# MAKO_pH_sensor_schematic.net
KiCad netlist of a schematic drawn in Altium Designer
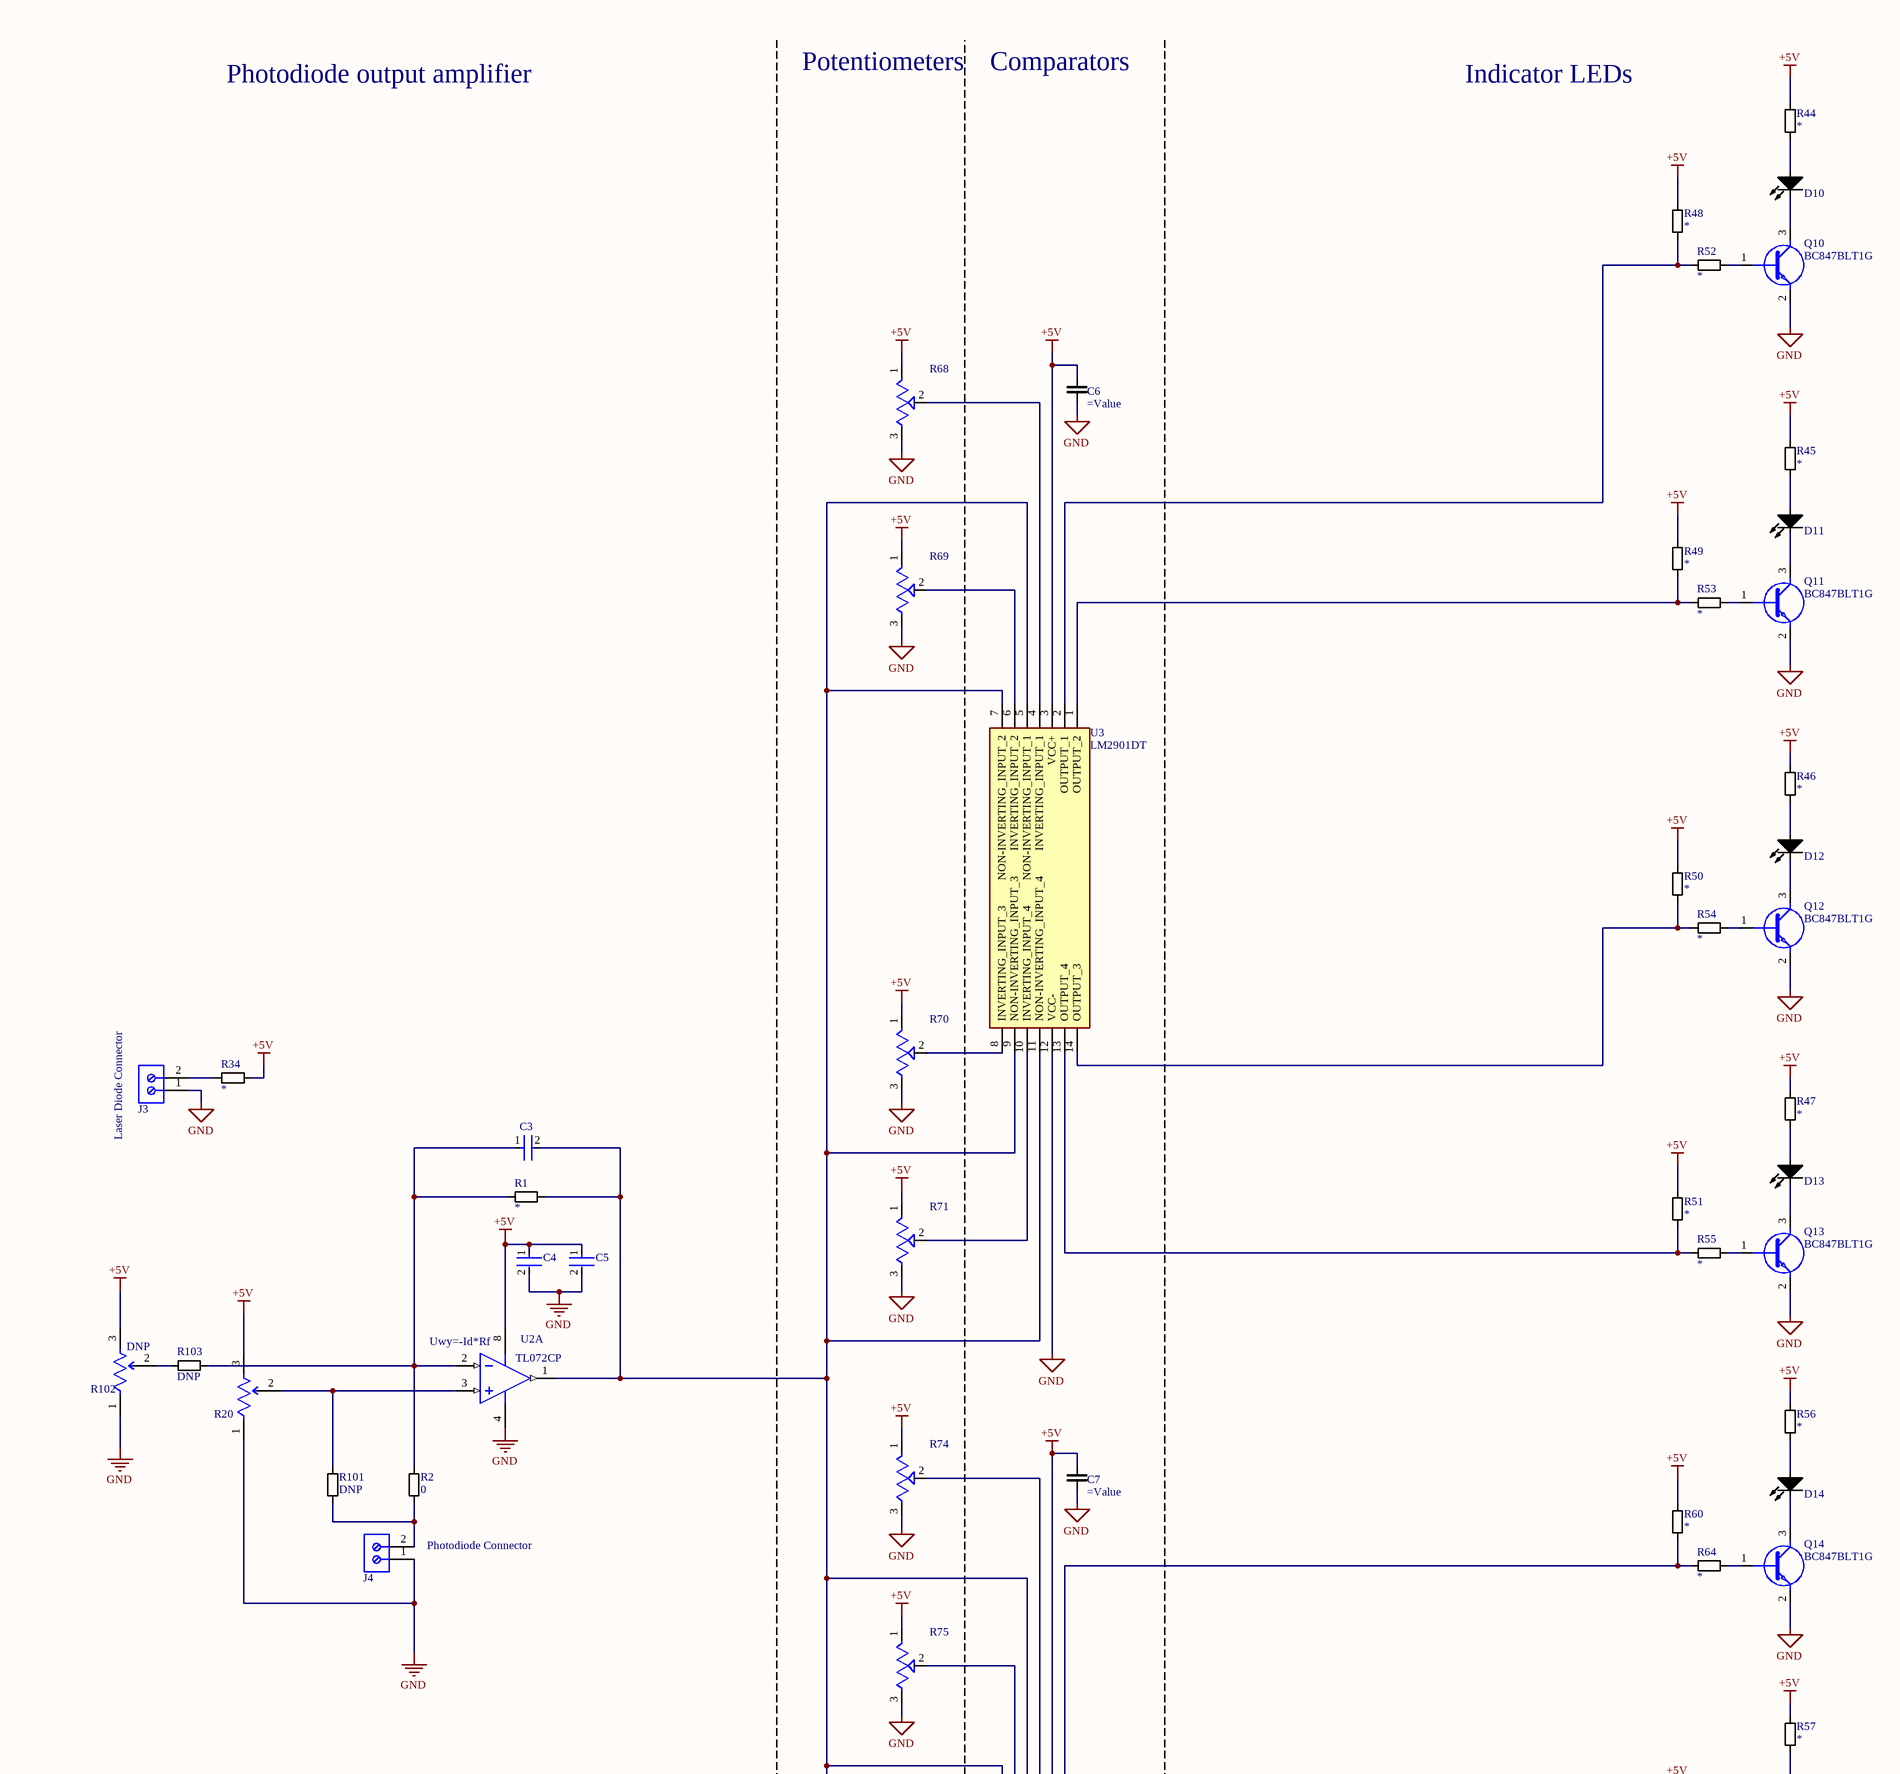
[diagram p0: MAKO_pH_sensor_schematic.SchDoc, top]
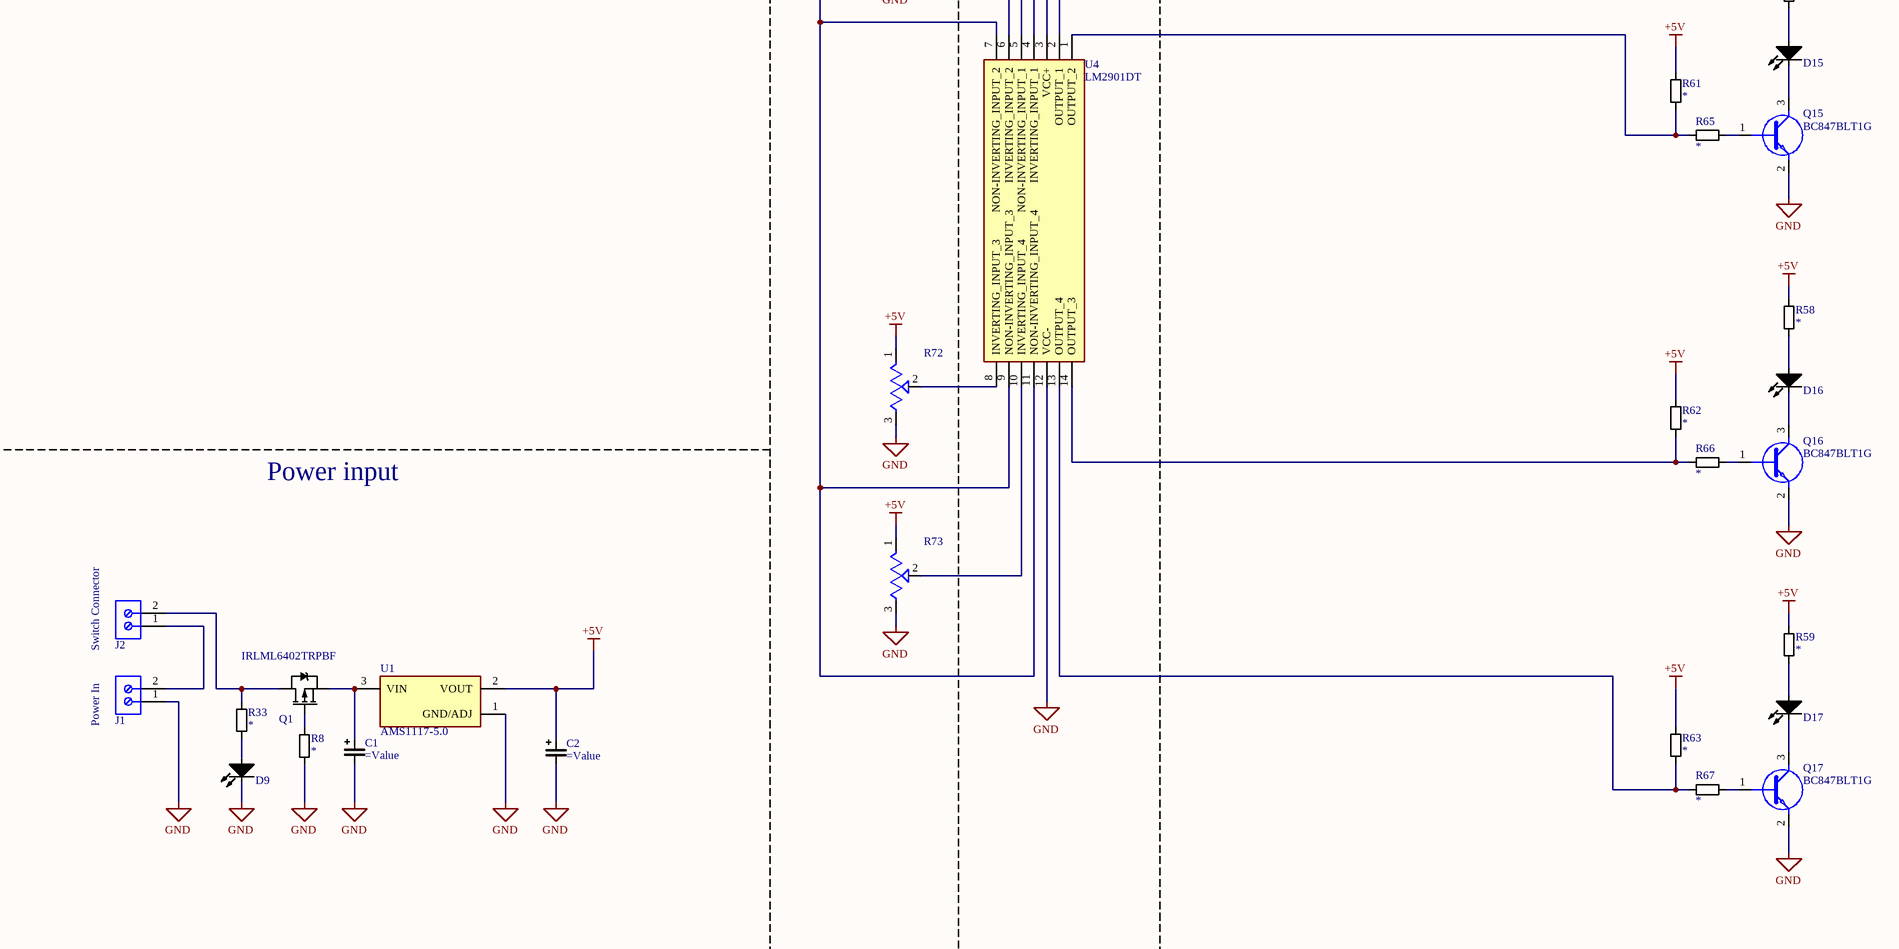
[diagram p1: MAKO_pH_sensor_schematic.SchDoc, bottom]

(export (version "E")
  (design (tool "Eeschema 10.0.6"))
  (components
    (comp (ref "C1")
      (value "~")
      (footprint "CAPAE530X610N:CAPAE530X610N")
      (description "Ceramic capacitor")
      (libsource (lib "Cap") (part "CapPol"))
    )
    (comp (ref "C2")
      (value "~")
      (footprint "CAPAE530X610N:CAPAE530X610N")
      (description "Ceramic capacitor")
      (libsource (lib "Cap") (part "CapPol"))
    )
    (comp (ref "C3")
      (value "C1206C102KGRACTU")
      (footprint "FP-C1206C-EF-MFG")
      (description "CAP CER 1000PF 2KV X7R 1206")
      (fields (field (name "VOLTAGE") "2kV") (field (name "TOLERANCE") "10%"))
      (libsource (lib "Altium Content Vault") (part "b4654b650e69147ec39a6b967a45e02"))
    )
    (comp (ref "C4")
      (value "C1206C104M5RACTU")
      (footprint "FP-C1206C-EB-MFG")
      (description "CAP CER 0.1UF 50V X7R 1206")
      (fields
        (field (name "OCTOPART") "https://octopart.com/c1206c104m5ractu-kemet-129344")
        (field (name "TOLERANCE") "0.2")
      )
      (libsource (lib "Altium Content Vault") (part "b4654b650e69147ec39a6b967a45e02"))
    )
    (comp (ref "C5")
      (value "C1206C104M5RACTU")
      (footprint "FP-C1206C-EB-MFG")
      (description "CAP CER 0.1UF 50V X7R 1206")
      (fields
        (field (name "OCTOPART") "https://octopart.com/c1206c104m5ractu-kemet-129344")
        (field (name "TOLERANCE") "0.2")
      )
      (libsource (lib "Altium Content Vault") (part "b4654b650e69147ec39a6b967a45e02"))
    )
    (comp (ref "C6")
      (value "~")
      (footprint "CAPC1608X90N")
      (description "Ceramic capacitor")
      (libsource (lib "Cap") (part "Cap"))
    )
    (comp (ref "C7")
      (value "~")
      (footprint "CAPC1608X90N")
      (description "Ceramic capacitor")
      (libsource (lib "Cap") (part "Cap"))
    )
    (comp (ref "D9")
      (value "~")
      (footprint "151033RS03000:151033RS03000")
      (libsource (lib "LED") (part "LED"))
    )
    (comp (ref "D10") (value "~") (footprint "151033RS03000") (libsource (lib "LED") (part "LED")))
    (comp (ref "D11") (value "~") (footprint "151033RS03000") (libsource (lib "LED") (part "LED")))
    (comp (ref "D12") (value "~") (footprint "151033RS03000") (libsource (lib "LED") (part "LED")))
    (comp (ref "D13") (value "~") (footprint "151033RS03000") (libsource (lib "LED") (part "LED")))
    (comp (ref "D14") (value "~") (footprint "151033RS03000") (libsource (lib "LED") (part "LED")))
    (comp (ref "D15")
      (value "~")
      (footprint "151033RS03000:151033RS03000")
      (libsource (lib "LED") (part "LED"))
    )
    (comp (ref "D16")
      (value "~")
      (footprint "151033RS03000:151033RS03000")
      (libsource (lib "LED") (part "LED"))
    )
    (comp (ref "D17")
      (value "~")
      (footprint "151033RS03000:151033RS03000")
      (libsource (lib "LED") (part "LED"))
    )
    (comp (ref "J1")
      (value "691101710002")
      (footprint "RHDRRA2W95P0X500_1X2_1120X900X1280P:RHDRRA2W95P0X500_1X2_1120X900X1280P")
      (description "WR-TBL Series 101 Horizontal Entry Modular, THT, pitch 5mm, 2p")
      (fields (field (name "MANUFACTURER") "Wurth Elektronik"))
      (libsource (lib "Altium_WR-TBL (rev23e)") (part "691101710002"))
    )
    (comp (ref "J2")
      (value "691101710002")
      (footprint "RHDRRA2W95P0X500_1X2_1120X900X1280P:RHDRRA2W95P0X500_1X2_1120X900X1280P")
      (description "WR-TBL Series 101 Horizontal Entry Modular, THT, pitch 5mm, 2p")
      (fields (field (name "MANUFACTURER") "Wurth Elektronik"))
      (libsource (lib "Altium_WR-TBL (rev23e)") (part "691101710002"))
    )
    (comp (ref "J3")
      (value "691101710002")
      (footprint "RHDRRA2W95P0X500_1X2_1120X900X1280P:RHDRRA2W95P0X500_1X2_1120X900X1280P")
      (description "WR-TBL Series 101 Horizontal Entry Modular, THT, pitch 5mm, 2p")
      (fields (field (name "MANUFACTURER") "Wurth Elektronik"))
      (libsource (lib "Altium_WR-TBL (rev23e)") (part "691101710002"))
    )
    (comp (ref "J4")
      (value "691101710002")
      (footprint "RHDRRA2W95P0X500_1X2_1120X900X1280P:RHDRRA2W95P0X500_1X2_1120X900X1280P")
      (description "WR-TBL Series 101 Horizontal Entry Modular, THT, pitch 5mm, 2p")
      (fields (field (name "MANUFACTURER") "Wurth Elektronik"))
      (libsource (lib "Altium_WR-TBL (rev23e)") (part "691101710002"))
    )
    (comp (ref "Q1")
      (value "IRLML6402TRPBF")
      (footprint "SOT95P237X112-3N:SOT95P237X112-3N")
      (libsource (lib "PMOSFET") (part "PMOSFET"))
    )
    (comp (ref "Q10")
      (value "BC847BLT1G")
      (footprint "SOT96P237X111-3N")
      (fields (field (name "MOUSER PART NUMBER") "863-BC847BLT1G"))
      (libsource (lib "BC847BLT1G") (part "BC847BLT1G"))
    )
    (comp (ref "Q11")
      (value "BC847BLT1G")
      (footprint "SOT96P237X111-3N")
      (fields (field (name "MOUSER PART NUMBER") "863-BC847BLT1G"))
      (libsource (lib "BC847BLT1G") (part "BC847BLT1G"))
    )
    (comp (ref "Q12")
      (value "BC847BLT1G")
      (footprint "SOT96P237X111-3N")
      (fields (field (name "MOUSER PART NUMBER") "863-BC847BLT1G"))
      (libsource (lib "BC847BLT1G") (part "BC847BLT1G"))
    )
    (comp (ref "Q13")
      (value "BC847BLT1G")
      (footprint "SOT96P237X111-3N")
      (fields (field (name "MOUSER PART NUMBER") "863-BC847BLT1G"))
      (libsource (lib "BC847BLT1G") (part "BC847BLT1G"))
    )
    (comp (ref "Q14")
      (value "BC847BLT1G")
      (footprint "SOT96P237X111-3N")
      (fields (field (name "MOUSER PART NUMBER") "863-BC847BLT1G"))
      (libsource (lib "BC847BLT1G") (part "BC847BLT1G"))
    )
    (comp (ref "Q15")
      (value "BC847BLT1G")
      (footprint "SOT96P237X111-3N")
      (fields (field (name "MOUSER PART NUMBER") "863-BC847BLT1G"))
      (libsource (lib "BC847BLT1G") (part "BC847BLT1G"))
    )
    (comp (ref "Q16")
      (value "BC847BLT1G")
      (footprint "SOT96P237X111-3N")
      (fields (field (name "MOUSER PART NUMBER") "863-BC847BLT1G"))
      (libsource (lib "BC847BLT1G") (part "BC847BLT1G"))
    )
    (comp (ref "Q17")
      (value "BC847BLT1G")
      (footprint "SOT96P237X111-3N")
      (fields (field (name "MOUSER PART NUMBER") "863-BC847BLT1G"))
      (libsource (lib "BC847BLT1G") (part "BC847BLT1G"))
    )
    (comp (ref "R1")
      (value "*")
      (footprint "CAPC1608X90N")
      (description "Resistor")
      (libsource (lib "RES") (part "RES"))
    )
    (comp (ref "R2")
      (value "0")
      (footprint "CAPC1608X90N")
      (description "Resistor")
      (libsource (lib "RES") (part "RES"))
    )
    (comp (ref "R8")
      (value "*")
      (footprint "CAPC1608X90N")
      (description "Resistor")
      (libsource (lib "RES") (part "RES"))
    )
    (comp (ref "R20")
      (value "3296W-1-103LF")
      (footprint "FP-3296W-MFG")
      (description "TRIMMER 10K OHM 0.5W PC PIN TOP\r\n3296W-1-103LF")
      (fields (field (name "TOLERANCE") "10%"))
      (libsource (lib "Altium Content Vault") (part "2dcfd2547301a7d3209a5e99acfd772"))
    )
    (comp (ref "R33")
      (value "*")
      (footprint "CAPC1608X90N")
      (description "Resistor")
      (libsource (lib "RES") (part "RES"))
    )
    (comp (ref "R34")
      (value "*")
      (footprint "CAPC1608X90N")
      (description "Resistor")
      (libsource (lib "RES") (part "RES"))
    )
    (comp (ref "R44")
      (value "*")
      (footprint "CAPC1608X90N")
      (description "Resistor")
      (libsource (lib "RES") (part "RES"))
    )
    (comp (ref "R45")
      (value "*")
      (footprint "CAPC1608X90N")
      (description "Resistor")
      (libsource (lib "RES") (part "RES"))
    )
    (comp (ref "R46")
      (value "*")
      (footprint "CAPC1608X90N")
      (description "Resistor")
      (libsource (lib "RES") (part "RES"))
    )
    (comp (ref "R47")
      (value "*")
      (footprint "CAPC1608X90N")
      (description "Resistor")
      (libsource (lib "RES") (part "RES"))
    )
    (comp (ref "R48")
      (value "*")
      (footprint "CAPC1608X90N")
      (description "Resistor")
      (libsource (lib "RES") (part "RES"))
    )
    (comp (ref "R49")
      (value "*")
      (footprint "CAPC1608X90N")
      (description "Resistor")
      (libsource (lib "RES") (part "RES"))
    )
    (comp (ref "R50")
      (value "*")
      (footprint "CAPC1608X90N")
      (description "Resistor")
      (libsource (lib "RES") (part "RES"))
    )
    (comp (ref "R51")
      (value "*")
      (footprint "CAPC1608X90N")
      (description "Resistor")
      (libsource (lib "RES") (part "RES"))
    )
    (comp (ref "R52")
      (value "*")
      (footprint "CAPC1608X90N")
      (description "Resistor")
      (libsource (lib "RES") (part "RES"))
    )
    (comp (ref "R53")
      (value "*")
      (footprint "CAPC1608X90N")
      (description "Resistor")
      (libsource (lib "RES") (part "RES"))
    )
    (comp (ref "R54")
      (value "*")
      (footprint "CAPC1608X90N")
      (description "Resistor")
      (libsource (lib "RES") (part "RES"))
    )
    (comp (ref "R55")
      (value "*")
      (footprint "CAPC1608X90N")
      (description "Resistor")
      (libsource (lib "RES") (part "RES"))
    )
    (comp (ref "R56")
      (value "*")
      (footprint "CAPC1608X90N")
      (description "Resistor")
      (libsource (lib "RES") (part "RES"))
    )
    (comp (ref "R57")
      (value "*")
      (footprint "CAPC1608X90N")
      (description "Resistor")
      (libsource (lib "RES") (part "RES"))
    )
    (comp (ref "R58")
      (value "*")
      (footprint "CAPC1608X90N")
      (description "Resistor")
      (libsource (lib "RES") (part "RES"))
    )
    (comp (ref "R59")
      (value "*")
      (footprint "CAPC1608X90N")
      (description "Resistor")
      (libsource (lib "RES") (part "RES"))
    )
    (comp (ref "R60")
      (value "*")
      (footprint "CAPC1608X90N")
      (description "Resistor")
      (libsource (lib "RES") (part "RES"))
    )
    (comp (ref "R61")
      (value "*")
      (footprint "CAPC1608X90N")
      (description "Resistor")
      (libsource (lib "RES") (part "RES"))
    )
    (comp (ref "R62")
      (value "*")
      (footprint "CAPC1608X90N")
      (description "Resistor")
      (libsource (lib "RES") (part "RES"))
    )
    (comp (ref "R63")
      (value "*")
      (footprint "CAPC1608X90N")
      (description "Resistor")
      (libsource (lib "RES") (part "RES"))
    )
    (comp (ref "R64")
      (value "*")
      (footprint "CAPC1608X90N")
      (description "Resistor")
      (libsource (lib "RES") (part "RES"))
    )
    (comp (ref "R65")
      (value "*")
      (footprint "CAPC1608X90N")
      (description "Resistor")
      (libsource (lib "RES") (part "RES"))
    )
    (comp (ref "R66")
      (value "*")
      (footprint "CAPC1608X90N")
      (description "Resistor")
      (libsource (lib "RES") (part "RES"))
    )
    (comp (ref "R67")
      (value "*")
      (footprint "CAPC1608X90N")
      (description "Resistor")
      (libsource (lib "RES") (part "RES"))
    )
    (comp (ref "R68")
      (value "WH06-2B-10K")
      (footprint "3306F1503:3306F1503")
      (description "10 kOhms 0.2W, 1/5W PC Pins Through Hole Trimmer Potentiometer Cermet 1 Turn Top Adjustment")
      (fields (field (name "MF") "Bourns") (field (name "MP") "3306F-1-103"))
      (libsource (lib "3306F-1-103") (part "3306F-1-103"))
    )
    (comp (ref "R69")
      (value "WH06-2B-10K")
      (footprint "3306F1503:3306F1503")
      (description "10 kOhms 0.2W, 1/5W PC Pins Through Hole Trimmer Potentiometer Cermet 1 Turn Top Adjustment")
      (fields (field (name "MF") "Bourns") (field (name "MP") "3306F-1-103"))
      (libsource (lib "3306F-1-103") (part "3306F-1-103"))
    )
    (comp (ref "R70")
      (value "WH06-2B-10K")
      (footprint "3306F1503:3306F1503")
      (description "10 kOhms 0.2W, 1/5W PC Pins Through Hole Trimmer Potentiometer Cermet 1 Turn Top Adjustment")
      (fields (field (name "MF") "Bourns") (field (name "MP") "3306F-1-103"))
      (libsource (lib "3306F-1-103") (part "3306F-1-103"))
    )
    (comp (ref "R71")
      (value "WH06-2B-10K")
      (footprint "3306F1503:3306F1503")
      (description "10 kOhms 0.2W, 1/5W PC Pins Through Hole Trimmer Potentiometer Cermet 1 Turn Top Adjustment")
      (fields (field (name "MF") "Bourns") (field (name "MP") "3306F-1-103"))
      (libsource (lib "3306F-1-103") (part "3306F-1-103"))
    )
    (comp (ref "R72")
      (value "WH06-2B-10K")
      (footprint "3306F1503:3306F1503")
      (description "10 kOhms 0.2W, 1/5W PC Pins Through Hole Trimmer Potentiometer Cermet 1 Turn Top Adjustment")
      (fields (field (name "MF") "Bourns") (field (name "MP") "3306F-1-103"))
      (libsource (lib "3306F-1-103") (part "3306F-1-103"))
    )
    (comp (ref "R73")
      (value "WH06-2B-10K")
      (footprint "3306F1503:3306F1503")
      (description "10 kOhms 0.2W, 1/5W PC Pins Through Hole Trimmer Potentiometer Cermet 1 Turn Top Adjustment")
      (fields (field (name "MF") "Bourns") (field (name "MP") "3306F-1-103"))
      (libsource (lib "3306F-1-103") (part "3306F-1-103"))
    )
    (comp (ref "R74")
      (value "WH06-2B-10K")
      (footprint "3306F1503:3306F1503")
      (description "10 kOhms 0.2W, 1/5W PC Pins Through Hole Trimmer Potentiometer Cermet 1 Turn Top Adjustment")
      (fields (field (name "MF") "Bourns") (field (name "MP") "3306F-1-103"))
      (libsource (lib "3306F-1-103") (part "3306F-1-103"))
    )
    (comp (ref "R75")
      (value "WH06-2B-10K")
      (footprint "3306F1503:3306F1503")
      (description "10 kOhms 0.2W, 1/5W PC Pins Through Hole Trimmer Potentiometer Cermet 1 Turn Top Adjustment")
      (fields (field (name "MF") "Bourns") (field (name "MP") "3306F-1-103"))
      (libsource (lib "3306F-1-103") (part "3306F-1-103"))
    )
    (comp (ref "R101")
      (value "DNP")
      (footprint "CAPC1608X90N")
      (description "Resistor")
      (libsource (lib "RES") (part "RES"))
    )
    (comp (ref "R102")
      (value "DNP")
      (footprint "FP-3296W-MFG")
      (description "TRIMMER 10K OHM 0.5W PC PIN TOP\r\n3296W-1-103LF")
      (fields (field (name "TOLERANCE") "10%"))
      (libsource (lib "Altium Content Vault") (part "2dcfd2547301a7d3209a5e99acfd772"))
    )
    (comp (ref "R103")
      (value "DNP")
      (footprint "CAPC1608X90N")
      (description "Resistor")
      (libsource (lib "RES") (part "RES"))
    )
    (comp (ref "U1")
      (value "AMS1117-5.0")
      (footprint "S402TS1RP:S402TS1RP")
      (description "1A LOW DROPOUT VOLTAGE REGULATOR")
      (fields (field (name "MF") "ams"))
      (libsource (lib "AMS1117-5.0") (part "AMS1117-5.0"))
    )
    (comp (ref "U2")
      (value "TL072CP")
      (footprint "P0008A")
      (fields (field (name "MANUFACTURER") "Texas Instruments"))
      (libsource (lib "Altium Content Vault") (part "TI-AMP-D6-2-8_D"))
    )
    (comp (ref "U3")
      (value "LM2901DT")
      (footprint "SOIC127P600X175-14N")
      (fields (field (name "MOUSER PART NUMBER") "511-LM2901DT"))
      (libsource (lib "LM2901DT") (part "LM2901DT"))
    )
    (comp (ref "U4")
      (value "LM2901DT")
      (footprint "SOIC127P600X175-14N")
      (fields (field (name "MOUSER PART NUMBER") "511-LM2901DT"))
      (libsource (lib "LM2901DT") (part "LM2901DT"))
    )
  )
  (nets
    (net (code "1") (name "+5V") (class "Default")
      (node (ref "C2") (pin "1") (pinfunction "1_1") (pintype "passive"))
      (node (ref "C4") (pin "1") (pinfunction "1_1") (pintype "passive"))
      (node (ref "C5") (pin "1") (pinfunction "1_1") (pintype "passive"))
      (node (ref "C6") (pin "2") (pinfunction "2_2") (pintype "passive"))
      (node (ref "C7") (pin "2") (pinfunction "2_2") (pintype "passive"))
      (node (ref "R102") (pin "3") (pinfunction "CW_3") (pintype "passive"))
      (node (ref "R20") (pin "3") (pinfunction "CW_3") (pintype "passive"))
      (node (ref "R34") (pin "1") (pinfunction "1_1") (pintype "passive"))
      (node (ref "R44") (pin "1") (pinfunction "1_1") (pintype "passive"))
      (node (ref "R45") (pin "1") (pinfunction "1_1") (pintype "passive"))
      (node (ref "R46") (pin "1") (pinfunction "1_1") (pintype "passive"))
      (node (ref "R47") (pin "1") (pinfunction "1_1") (pintype "passive"))
      (node (ref "R48") (pin "1") (pinfunction "1_1") (pintype "passive"))
      (node (ref "R49") (pin "1") (pinfunction "1_1") (pintype "passive"))
      (node (ref "R50") (pin "1") (pinfunction "1_1") (pintype "passive"))
      (node (ref "R51") (pin "1") (pinfunction "1_1") (pintype "passive"))
      (node (ref "R56") (pin "1") (pinfunction "1_1") (pintype "passive"))
      (node (ref "R57") (pin "1") (pinfunction "1_1") (pintype "passive"))
      (node (ref "R58") (pin "1") (pinfunction "1_1") (pintype "passive"))
      (node (ref "R59") (pin "1") (pinfunction "1_1") (pintype "passive"))
      (node (ref "R60") (pin "1") (pinfunction "1_1") (pintype "passive"))
      (node (ref "R61") (pin "1") (pinfunction "1_1") (pintype "passive"))
      (node (ref "R62") (pin "1") (pinfunction "1_1") (pintype "passive"))
      (node (ref "R63") (pin "1") (pinfunction "1_1") (pintype "passive"))
      (node (ref "R68") (pin "1") (pinfunction "CCW_1") (pintype "passive"))
      (node (ref "R69") (pin "1") (pinfunction "CCW_1") (pintype "passive"))
      (node (ref "R70") (pin "1") (pinfunction "CCW_1") (pintype "passive"))
      (node (ref "R71") (pin "1") (pinfunction "CCW_1") (pintype "passive"))
      (node (ref "R72") (pin "1") (pinfunction "CCW_1") (pintype "passive"))
      (node (ref "R73") (pin "1") (pinfunction "CCW_1") (pintype "passive"))
      (node (ref "R74") (pin "1") (pinfunction "CCW_1") (pintype "passive"))
      (node (ref "R75") (pin "1") (pinfunction "CCW_1") (pintype "passive"))
      (node (ref "U1") (pin "2") (pinfunction "VOUT_2") (pintype "power_in"))
      (node (ref "U2") (pin "8") (pinfunction "VCC+_8") (pintype "power_in"))
      (node (ref "U3") (pin "3") (pinfunction "VCC+_3") (pintype "passive"))
      (node (ref "U4") (pin "3") (pinfunction "VCC+_3") (pintype "passive"))
    )
    (net (code "2") (name "GND") (class "Default")
      (node (ref "C1") (pin "2") (pinfunction "2_2") (pintype "passive"))
      (node (ref "C2") (pin "2") (pinfunction "2_2") (pintype "passive"))
      (node (ref "C4") (pin "2") (pinfunction "2_2") (pintype "passive"))
      (node (ref "C5") (pin "2") (pinfunction "2_2") (pintype "passive"))
      (node (ref "C6") (pin "1") (pinfunction "1_1") (pintype "passive"))
      (node (ref "C7") (pin "1") (pinfunction "1_1") (pintype "passive"))
      (node (ref "D9") (pin "2") (pinfunction "K_2") (pintype "passive"))
      (node (ref "J1") (pin "1") (pinfunction "1_1") (pintype "passive"))
      (node (ref "J3") (pin "1") (pinfunction "1_1") (pintype "passive"))
      (node (ref "J4") (pin "1") (pinfunction "1_1") (pintype "passive"))
      (node (ref "Q10") (pin "2") (pinfunction "E_2") (pintype "passive"))
      (node (ref "Q11") (pin "2") (pinfunction "E_2") (pintype "passive"))
      (node (ref "Q12") (pin "2") (pinfunction "E_2") (pintype "passive"))
      (node (ref "Q13") (pin "2") (pinfunction "E_2") (pintype "passive"))
      (node (ref "Q14") (pin "2") (pinfunction "E_2") (pintype "passive"))
      (node (ref "Q15") (pin "2") (pinfunction "E_2") (pintype "passive"))
      (node (ref "Q16") (pin "2") (pinfunction "E_2") (pintype "passive"))
      (node (ref "Q17") (pin "2") (pinfunction "E_2") (pintype "passive"))
      (node (ref "R102") (pin "1") (pinfunction "CCW_1") (pintype "passive"))
      (node (ref "R20") (pin "1") (pinfunction "CCW_1") (pintype "passive"))
      (node (ref "R68") (pin "3") (pinfunction "CW_3") (pintype "passive"))
      (node (ref "R69") (pin "3") (pinfunction "CW_3") (pintype "passive"))
      (node (ref "R70") (pin "3") (pinfunction "CW_3") (pintype "passive"))
      (node (ref "R71") (pin "3") (pinfunction "CW_3") (pintype "passive"))
      (node (ref "R72") (pin "3") (pinfunction "CW_3") (pintype "passive"))
      (node (ref "R73") (pin "3") (pinfunction "CW_3") (pintype "passive"))
      (node (ref "R74") (pin "3") (pinfunction "CW_3") (pintype "passive"))
      (node (ref "R75") (pin "3") (pinfunction "CW_3") (pintype "passive"))
      (node (ref "R8") (pin "1") (pinfunction "1_1") (pintype "passive"))
      (node (ref "U1") (pin "1") (pinfunction "GND/ADJ_1") (pintype "power_in"))
      (node (ref "U2") (pin "4") (pinfunction "VCC-_4") (pintype "power_in"))
      (node (ref "U3") (pin "12") (pinfunction "VCC-_12") (pintype "passive"))
      (node (ref "U4") (pin "12") (pinfunction "VCC-_12") (pintype "passive"))
    )
    (net (code "3") (name "Net-(D9-A)") (class "Default")
      (node (ref "D9") (pin "1") (pinfunction "A_1") (pintype "passive"))
      (node (ref "R33") (pin "2") (pinfunction "2_2") (pintype "passive"))
    )
    (net (code "4") (name "Net-(D10-A)") (class "Default")
      (node (ref "D10") (pin "1") (pinfunction "A_1") (pintype "passive"))
      (node (ref "R44") (pin "2") (pinfunction "2_2") (pintype "passive"))
    )
    (net (code "5") (name "Net-(D10-K)") (class "Default")
      (node (ref "D10") (pin "2") (pinfunction "K_2") (pintype "passive"))
      (node (ref "Q10") (pin "3") (pinfunction "C_3") (pintype "passive"))
    )
    (net (code "6") (name "Net-(D11-A)") (class "Default")
      (node (ref "D11") (pin "1") (pinfunction "A_1") (pintype "passive"))
      (node (ref "R45") (pin "2") (pinfunction "2_2") (pintype "passive"))
    )
    (net (code "7") (name "Net-(D11-K)") (class "Default")
      (node (ref "D11") (pin "2") (pinfunction "K_2") (pintype "passive"))
      (node (ref "Q11") (pin "3") (pinfunction "C_3") (pintype "passive"))
    )
    (net (code "8") (name "Net-(D12-A)") (class "Default")
      (node (ref "D12") (pin "1") (pinfunction "A_1") (pintype "passive"))
      (node (ref "R46") (pin "2") (pinfunction "2_2") (pintype "passive"))
    )
    (net (code "9") (name "Net-(D12-K)") (class "Default")
      (node (ref "D12") (pin "2") (pinfunction "K_2") (pintype "passive"))
      (node (ref "Q12") (pin "3") (pinfunction "C_3") (pintype "passive"))
    )
    (net (code "10") (name "Net-(D13-A)") (class "Default")
      (node (ref "D13") (pin "1") (pinfunction "A_1") (pintype "passive"))
      (node (ref "R47") (pin "2") (pinfunction "2_2") (pintype "passive"))
    )
    (net (code "11") (name "Net-(D13-K)") (class "Default")
      (node (ref "D13") (pin "2") (pinfunction "K_2") (pintype "passive"))
      (node (ref "Q13") (pin "3") (pinfunction "C_3") (pintype "passive"))
    )
    (net (code "12") (name "Net-(D14-A)") (class "Default")
      (node (ref "D14") (pin "1") (pinfunction "A_1") (pintype "passive"))
      (node (ref "R56") (pin "2") (pinfunction "2_2") (pintype "passive"))
    )
    (net (code "13") (name "Net-(D14-K)") (class "Default")
      (node (ref "D14") (pin "2") (pinfunction "K_2") (pintype "passive"))
      (node (ref "Q14") (pin "3") (pinfunction "C_3") (pintype "passive"))
    )
    (net (code "14") (name "Net-(D15-A)") (class "Default")
      (node (ref "D15") (pin "1") (pinfunction "A_1") (pintype "passive"))
      (node (ref "R57") (pin "2") (pinfunction "2_2") (pintype "passive"))
    )
    (net (code "15") (name "Net-(D15-K)") (class "Default")
      (node (ref "D15") (pin "2") (pinfunction "K_2") (pintype "passive"))
      (node (ref "Q15") (pin "3") (pinfunction "C_3") (pintype "passive"))
    )
    (net (code "16") (name "Net-(D16-A)") (class "Default")
      (node (ref "D16") (pin "1") (pinfunction "A_1") (pintype "passive"))
      (node (ref "R58") (pin "2") (pinfunction "2_2") (pintype "passive"))
    )
    (net (code "17") (name "Net-(D16-K)") (class "Default")
      (node (ref "D16") (pin "2") (pinfunction "K_2") (pintype "passive"))
      (node (ref "Q16") (pin "3") (pinfunction "C_3") (pintype "passive"))
    )
    (net (code "18") (name "Net-(D17-A)") (class "Default")
      (node (ref "D17") (pin "1") (pinfunction "A_1") (pintype "passive"))
      (node (ref "R59") (pin "2") (pinfunction "2_2") (pintype "passive"))
    )
    (net (code "19") (name "Net-(D17-K)") (class "Default")
      (node (ref "D17") (pin "2") (pinfunction "K_2") (pintype "passive"))
      (node (ref "Q17") (pin "3") (pinfunction "C_3") (pintype "passive"))
    )
    (net (code "20") (name "Net-(J1-Pad2)") (class "Default")
      (node (ref "J1") (pin "2") (pinfunction "2_2") (pintype "passive"))
      (node (ref "J2") (pin "1") (pinfunction "1_1") (pintype "passive"))
    )
    (net (code "21") (name "Net-(J3-Pad2)") (class "Default")
      (node (ref "J3") (pin "2") (pinfunction "2_2") (pintype "passive"))
      (node (ref "R34") (pin "2") (pinfunction "2_2") (pintype "passive"))
    )
    (net (code "22") (name "Net-(J4-Pad2)") (class "Default")
      (node (ref "J4") (pin "2") (pinfunction "2_2") (pintype "passive"))
      (node (ref "R101") (pin "1") (pinfunction "1_1") (pintype "passive"))
      (node (ref "R2") (pin "1") (pinfunction "1_1") (pintype "passive"))
    )
    (net (code "23") (name "Net-(Q1-D)") (class "Default")
      (node (ref "J2") (pin "2") (pinfunction "2_2") (pintype "passive"))
      (node (ref "Q1") (pin "2") (pinfunction "D_2") (pintype "passive"))
      (node (ref "R33") (pin "1") (pinfunction "1_1") (pintype "passive"))
    )
    (net (code "24") (name "Net-(Q1-G)") (class "Default")
      (node (ref "Q1") (pin "1") (pinfunction "G_1") (pintype "passive"))
      (node (ref "R8") (pin "2") (pinfunction "2_2") (pintype "passive"))
    )
    (net (code "25") (name "Net-(Q1-S)") (class "Default")
      (node (ref "C1") (pin "1") (pinfunction "1_1") (pintype "passive"))
      (node (ref "Q1") (pin "3") (pinfunction "S_3") (pintype "passive"))
      (node (ref "U1") (pin "3") (pinfunction "VIN_3") (pintype "power_in"))
    )
    (net (code "26") (name "Net-(Q10-B)") (class "Default")
      (node (ref "Q10") (pin "1") (pinfunction "B_1") (pintype "passive"))
      (node (ref "R52") (pin "1") (pinfunction "1_1") (pintype "passive"))
    )
    (net (code "27") (name "Net-(Q11-B)") (class "Default")
      (node (ref "Q11") (pin "1") (pinfunction "B_1") (pintype "passive"))
      (node (ref "R53") (pin "1") (pinfunction "1_1") (pintype "passive"))
    )
    (net (code "28") (name "Net-(Q12-B)") (class "Default")
      (node (ref "Q12") (pin "1") (pinfunction "B_1") (pintype "passive"))
      (node (ref "R54") (pin "1") (pinfunction "1_1") (pintype "passive"))
    )
    (net (code "29") (name "Net-(Q13-B)") (class "Default")
      (node (ref "Q13") (pin "1") (pinfunction "B_1") (pintype "passive"))
      (node (ref "R55") (pin "1") (pinfunction "1_1") (pintype "passive"))
    )
    (net (code "30") (name "Net-(Q14-B)") (class "Default")
      (node (ref "Q14") (pin "1") (pinfunction "B_1") (pintype "passive"))
      (node (ref "R64") (pin "1") (pinfunction "1_1") (pintype "passive"))
    )
    (net (code "31") (name "Net-(Q15-B)") (class "Default")
      (node (ref "Q15") (pin "1") (pinfunction "B_1") (pintype "passive"))
      (node (ref "R65") (pin "1") (pinfunction "1_1") (pintype "passive"))
    )
    (net (code "32") (name "Net-(Q16-B)") (class "Default")
      (node (ref "Q16") (pin "1") (pinfunction "B_1") (pintype "passive"))
      (node (ref "R66") (pin "1") (pinfunction "1_1") (pintype "passive"))
    )
    (net (code "33") (name "Net-(Q17-B)") (class "Default")
      (node (ref "Q17") (pin "1") (pinfunction "B_1") (pintype "passive"))
      (node (ref "R67") (pin "1") (pinfunction "1_1") (pintype "passive"))
    )
    (net (code "34") (name "Net-(R20-WIPER)") (class "Default")
      (node (ref "R101") (pin "2") (pinfunction "2_2") (pintype "passive"))
      (node (ref "R20") (pin "2") (pinfunction "WIPER_2") (pintype "passive"))
      (node (ref "U2") (pin "3") (pinfunction "IN1+_3") (pintype "input"))
    )
    (net (code "35") (name "Net-(R68-W)") (class "Default")
      (node (ref "R68") (pin "2") (pinfunction "W_2") (pintype "passive"))
      (node (ref "U3") (pin "4") (pinfunction "INVERTING_INPUT_1_4") (pintype "passive"))
    )
    (net (code "36") (name "Net-(R69-W)") (class "Default")
      (node (ref "R69") (pin "2") (pinfunction "W_2") (pintype "passive"))
      (node (ref "U3") (pin "6") (pinfunction "INVERTING_INPUT_2_6") (pintype "passive"))
    )
    (net (code "37") (name "Net-(R70-W)") (class "Default")
      (node (ref "R70") (pin "2") (pinfunction "W_2") (pintype "passive"))
      (node (ref "U3") (pin "8") (pinfunction "INVERTING_INPUT_3_8") (pintype "passive"))
    )
    (net (code "38") (name "Net-(R71-W)") (class "Default")
      (node (ref "R71") (pin "2") (pinfunction "W_2") (pintype "passive"))
      (node (ref "U3") (pin "10") (pinfunction "INVERTING_INPUT_4_10") (pintype "passive"))
    )
    (net (code "39") (name "Net-(R72-W)") (class "Default")
      (node (ref "R72") (pin "2") (pinfunction "W_2") (pintype "passive"))
      (node (ref "U4") (pin "8") (pinfunction "INVERTING_INPUT_3_8") (pintype "passive"))
    )
    (net (code "40") (name "Net-(R73-W)") (class "Default")
      (node (ref "R73") (pin "2") (pinfunction "W_2") (pintype "passive"))
      (node (ref "U4") (pin "10") (pinfunction "INVERTING_INPUT_4_10") (pintype "passive"))
    )
    (net (code "41") (name "Net-(R74-W)") (class "Default")
      (node (ref "R74") (pin "2") (pinfunction "W_2") (pintype "passive"))
      (node (ref "U4") (pin "4") (pinfunction "INVERTING_INPUT_1_4") (pintype "passive"))
    )
    (net (code "42") (name "Net-(R75-W)") (class "Default")
      (node (ref "R75") (pin "2") (pinfunction "W_2") (pintype "passive"))
      (node (ref "U4") (pin "6") (pinfunction "INVERTING_INPUT_2_6") (pintype "passive"))
    )
    (net (code "43") (name "Net-(R102-WIPER)") (class "Default")
      (node (ref "R102") (pin "2") (pinfunction "WIPER_2") (pintype "passive"))
      (node (ref "R103") (pin "2") (pinfunction "2_2") (pintype "passive"))
    )
    (net (code "44") (name "Net-(U2A-IN1-)") (class "Default")
      (node (ref "C3") (pin "1") (pinfunction "1_1") (pintype "passive"))
      (node (ref "R1") (pin "1") (pinfunction "1_1") (pintype "passive"))
      (node (ref "R103") (pin "1") (pinfunction "1_1") (pintype "passive"))
      (node (ref "R2") (pin "2") (pinfunction "2_2") (pintype "passive"))
      (node (ref "U2") (pin "2") (pinfunction "IN1-_2") (pintype "input"))
    )
    (net (code "45") (name "Net-(U2A-OUT1)") (class "Default")
      (node (ref "C3") (pin "2") (pinfunction "2_2") (pintype "passive"))
      (node (ref "R1") (pin "2") (pinfunction "2_2") (pintype "passive"))
      (node (ref "U2") (pin "1") (pinfunction "OUT1_1") (pintype "output"))
      (node (ref "U3") (pin "11") (pinfunction "NON-INVERTING_INPUT_4_11") (pintype "passive"))
      (node (ref "U3") (pin "5") (pinfunction "NON-INVERTING_INPUT_1_5") (pintype "passive"))
      (node (ref "U3") (pin "7") (pinfunction "NON-INVERTING_INPUT_2_7") (pintype "passive"))
      (node (ref "U3") (pin "9") (pinfunction "NON-INVERTING_INPUT_3_9") (pintype "passive"))
      (node (ref "U4") (pin "11") (pinfunction "NON-INVERTING_INPUT_4_11") (pintype "passive"))
      (node (ref "U4") (pin "5") (pinfunction "NON-INVERTING_INPUT_1_5") (pintype "passive"))
      (node (ref "U4") (pin "7") (pinfunction "NON-INVERTING_INPUT_2_7") (pintype "passive"))
      (node (ref "U4") (pin "9") (pinfunction "NON-INVERTING_INPUT_3_9") (pintype "passive"))
    )
    (net (code "46") (name "Net-(U3-OUTPUT_1)") (class "Default")
      (node (ref "R48") (pin "2") (pinfunction "2_2") (pintype "passive"))
      (node (ref "R52") (pin "2") (pinfunction "2_2") (pintype "passive"))
      (node (ref "U3") (pin "2") (pinfunction "OUTPUT_1_2") (pintype "passive"))
    )
    (net (code "47") (name "Net-(U3-OUTPUT_2)") (class "Default")
      (node (ref "R49") (pin "2") (pinfunction "2_2") (pintype "passive"))
      (node (ref "R53") (pin "2") (pinfunction "2_2") (pintype "passive"))
      (node (ref "U3") (pin "1") (pinfunction "OUTPUT_2_1") (pintype "passive"))
    )
    (net (code "48") (name "Net-(U3-OUTPUT_3)") (class "Default")
      (node (ref "R50") (pin "2") (pinfunction "2_2") (pintype "passive"))
      (node (ref "R54") (pin "2") (pinfunction "2_2") (pintype "passive"))
      (node (ref "U3") (pin "14") (pinfunction "OUTPUT_3_14") (pintype "passive"))
    )
    (net (code "49") (name "Net-(U3-OUTPUT_4)") (class "Default")
      (node (ref "R51") (pin "2") (pinfunction "2_2") (pintype "passive"))
      (node (ref "R55") (pin "2") (pinfunction "2_2") (pintype "passive"))
      (node (ref "U3") (pin "13") (pinfunction "OUTPUT_4_13") (pintype "passive"))
    )
    (net (code "50") (name "Net-(U4-OUTPUT_1)") (class "Default")
      (node (ref "R60") (pin "2") (pinfunction "2_2") (pintype "passive"))
      (node (ref "R64") (pin "2") (pinfunction "2_2") (pintype "passive"))
      (node (ref "U4") (pin "2") (pinfunction "OUTPUT_1_2") (pintype "passive"))
    )
    (net (code "51") (name "Net-(U4-OUTPUT_2)") (class "Default")
      (node (ref "R61") (pin "2") (pinfunction "2_2") (pintype "passive"))
      (node (ref "R65") (pin "2") (pinfunction "2_2") (pintype "passive"))
      (node (ref "U4") (pin "1") (pinfunction "OUTPUT_2_1") (pintype "passive"))
    )
    (net (code "52") (name "Net-(U4-OUTPUT_3)") (class "Default")
      (node (ref "R62") (pin "2") (pinfunction "2_2") (pintype "passive"))
      (node (ref "R66") (pin "2") (pinfunction "2_2") (pintype "passive"))
      (node (ref "U4") (pin "14") (pinfunction "OUTPUT_3_14") (pintype "passive"))
    )
    (net (code "53") (name "Net-(U4-OUTPUT_4)") (class "Default")
      (node (ref "R63") (pin "2") (pinfunction "2_2") (pintype "passive"))
      (node (ref "R67") (pin "2") (pinfunction "2_2") (pintype "passive"))
      (node (ref "U4") (pin "13") (pinfunction "OUTPUT_4_13") (pintype "passive"))
    )
  )
)
